# picopower.net
KiCad netlist of a schematic drawn in EAGLE
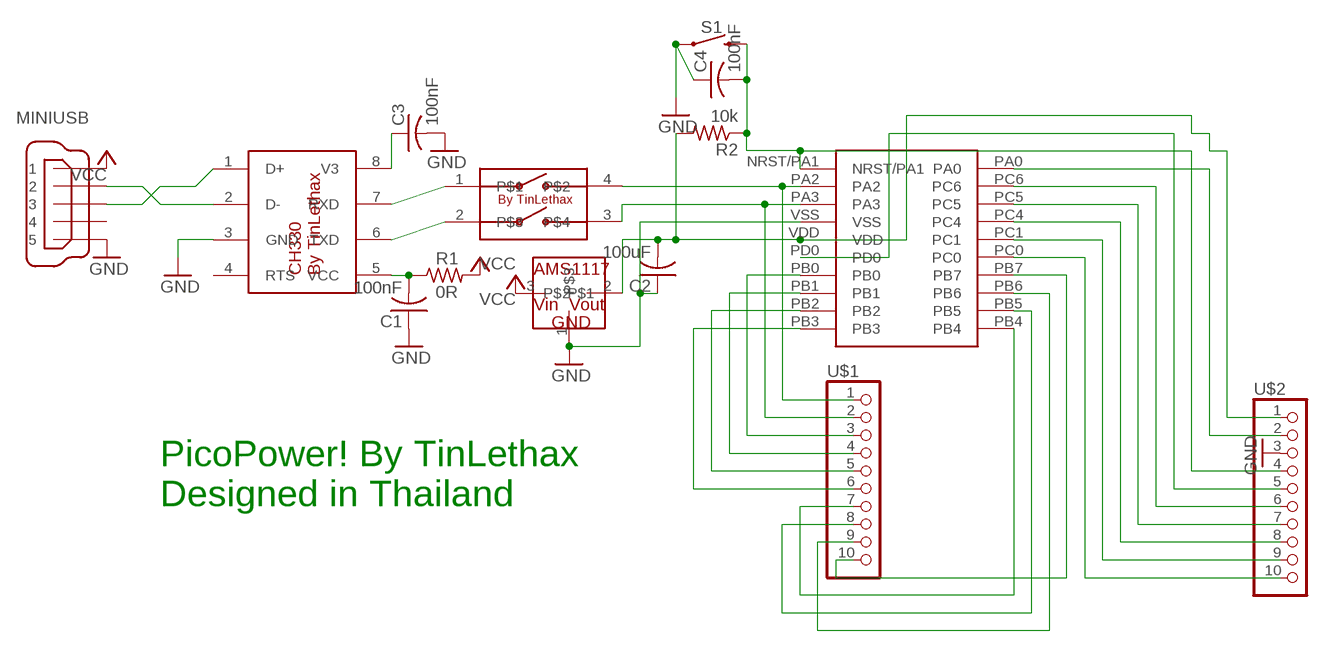
[diagram p0: schematic, sheet 1]

(export (version "E")
  (design (tool "Eeschema 10.0.6"))
  (components
    (comp (ref "2DIP")
      (value "2DIPSWITCH")
      (footprint "eagle-import:SOIC127P835X230-4N")
      (libsource (lib "eagle-import") (part "2DIPSWITCH"))
    )
    (comp (ref "C1")
      (value "100nF")
      (footprint "eagle-import:C0603K")
      (libsource (lib "eagle-import") (part "C-USC0603K"))
    )
    (comp (ref "C2")
      (value "100uF")
      (footprint "eagle-import:C0603K")
      (libsource (lib "eagle-import") (part "C-USC0603K"))
    )
    (comp (ref "C3")
      (value "100nF")
      (footprint "eagle-import:C0603K")
      (libsource (lib "eagle-import") (part "C-USC0603K"))
    )
    (comp (ref "C4")
      (value "100nF")
      (footprint "eagle-import:C0603K")
      (libsource (lib "eagle-import") (part "C-USC0603K"))
    )
    (comp (ref "CH330")
      (value "CH330")
      (footprint "eagle-import:SOIC127P600X150-8N")
      (libsource (lib "eagle-import") (part "CH330"))
    )
    (comp (ref "MINIUSB")
      (value "MINI-USB-UX60A-MB-5ST")
      (footprint "eagle-import:UX60A-MB-5ST")
      (libsource (lib "eagle-import") (part "MINI-USB-UX60A-MB-5ST"))
    )
    (comp (ref "R1")
      (value "0R")
      (footprint "eagle-import:R0603")
      (libsource (lib "eagle-import") (part "R-US_R0603"))
    )
    (comp (ref "R2")
      (value "10k")
      (footprint "eagle-import:R0603")
      (libsource (lib "eagle-import") (part "R-US_R0603"))
    )
    (comp (ref "S1")
      (value "MOMENTARY-SWITCH-SPST-SMD-6.0X3.5MM")
      (footprint "eagle-import:TACTILE_SWITCH_SMD_6.0X3.5MM")
      (libsource (lib "eagle-import") (part "MOMENTARY-SWITCH-SPST-SMD-6.0X3.5MM"))
    )
    (comp (ref "STM8L")
      (value "STM8L151F3")
      (footprint "eagle-import:UFQFPN-20")
      (libsource (lib "eagle-import") (part "STM8L151F3"))
    )
    (comp (ref "U$1")
      (value "PINHD-1X10")
      (footprint "eagle-import:1X10-BIG")
      (libsource (lib "eagle-import") (part "PINHD-1X10"))
    )
    (comp (ref "U$2")
      (value "PINHD-1X10")
      (footprint "eagle-import:1X10-BIG")
      (libsource (lib "eagle-import") (part "PINHD-1X10"))
    )
    (comp (ref "U$3")
      (value "AMS1117")
      (footprint "eagle-import:SOT223")
      (libsource (lib "eagle-import") (part "AMS1117"))
    )
  )
  (nets
    (net (code "1") (name "GND") (class "Default")
      (node (ref "C1") (pin "1") (pinfunction "1_1") (pintype "passive"))
      (node (ref "C2") (pin "1") (pinfunction "1_1") (pintype "passive"))
      (node (ref "C3") (pin "2") (pinfunction "2_2") (pintype "passive"))
      (node (ref "C4") (pin "1") (pinfunction "1_1") (pintype "passive"))
      (node (ref "CH330") (pin "3") (pinfunction "GND_3") (pintype "bidirectional"))
      (node (ref "MINIUSB") (pin "5") (pinfunction "5_5") (pintype "input"))
      (node (ref "S1") (pin "1") (pinfunction "1_1") (pintype "passive"))
      (node (ref "STM8L") (pin "VSS") (pinfunction "VSS_VSS") (pintype "bidirectional"))
      (node (ref "U$2") (pin "3") (pinfunction "3_3") (pintype "passive"))
      (node (ref "U$3") (pin "1") (pinfunction "P$3_1") (pintype "bidirectional"))
    )
    (net (code "2") (name "Net-(2DIP-P$1)") (class "Default")
      (node (ref "2DIP") (pin "1") (pinfunction "P$1_1") (pintype "bidirectional"))
      (node (ref "CH330") (pin "7") (pinfunction "RXD_7") (pintype "bidirectional"))
    )
    (net (code "3") (name "Net-(2DIP-P$2)") (class "Default")
      (node (ref "2DIP") (pin "4") (pinfunction "P$2_4") (pintype "bidirectional"))
      (node (ref "STM8L") (pin "PA2") (pinfunction "PA2_PA2") (pintype "bidirectional"))
      (node (ref "U$1") (pin "1") (pinfunction "1_1") (pintype "passive"))
    )
    (net (code "4") (name "Net-(2DIP-P$3)") (class "Default")
      (node (ref "2DIP") (pin "2") (pinfunction "P$3_2") (pintype "bidirectional"))
      (node (ref "CH330") (pin "6") (pinfunction "TXD_6") (pintype "bidirectional"))
    )
    (net (code "5") (name "Net-(2DIP-P$4)") (class "Default")
      (node (ref "2DIP") (pin "3") (pinfunction "P$4_3") (pintype "bidirectional"))
      (node (ref "STM8L") (pin "PA3") (pinfunction "PA3_PA3") (pintype "bidirectional"))
      (node (ref "U$1") (pin "2") (pinfunction "2_2") (pintype "passive"))
    )
    (net (code "6") (name "Net-(C4-Pad2)") (class "Default")
      (node (ref "C4") (pin "2") (pinfunction "2_2") (pintype "passive"))
      (node (ref "R2") (pin "1") (pinfunction "1_1") (pintype "passive"))
      (node (ref "S1") (pin "2") (pinfunction "2_2") (pintype "passive"))
      (node (ref "STM8L") (pin "NRST/PA1") (pinfunction "NRST/PA1_NRST/PA1") (pintype "bidirectional"))
      (node (ref "U$2") (pin "4") (pinfunction "4_4") (pintype "passive"))
    )
    (net (code "7") (name "Net-(CH330-D+)") (class "Default")
      (node (ref "CH330") (pin "1") (pinfunction "D+_1") (pintype "bidirectional"))
      (node (ref "MINIUSB") (pin "3") (pinfunction "3_3") (pintype "input"))
    )
    (net (code "8") (name "Net-(CH330-D-)") (class "Default")
      (node (ref "CH330") (pin "2") (pinfunction "D-_2") (pintype "bidirectional"))
      (node (ref "MINIUSB") (pin "2") (pinfunction "2_2") (pintype "input"))
    )
    (net (code "9") (name "Net-(CH330-V3)") (class "Default")
      (node (ref "C3") (pin "1") (pinfunction "1_1") (pintype "passive"))
      (node (ref "CH330") (pin "8") (pinfunction "V3_8") (pintype "bidirectional"))
    )
    (net (code "10") (name "Net-(CH330-VCC)") (class "Default")
      (node (ref "C1") (pin "2") (pinfunction "2_2") (pintype "passive"))
      (node (ref "CH330") (pin "5") (pinfunction "VCC_5") (pintype "bidirectional"))
      (node (ref "R1") (pin "1") (pinfunction "1_1") (pintype "passive"))
    )
    (net (code "11") (name "Net-(STM8L-PadPA0)") (class "Default")
      (node (ref "STM8L") (pin "PA0") (pinfunction "PA0_PA0") (pintype "bidirectional"))
      (node (ref "U$2") (pin "2") (pinfunction "2_2") (pintype "passive"))
    )
    (net (code "12") (name "Net-(STM8L-PadPB0)") (class "Default")
      (node (ref "STM8L") (pin "PB0") (pinfunction "PB0_PB0") (pintype "bidirectional"))
      (node (ref "U$1") (pin "3") (pinfunction "3_3") (pintype "passive"))
    )
    (net (code "13") (name "Net-(STM8L-PadPB1)") (class "Default")
      (node (ref "STM8L") (pin "PB1") (pinfunction "PB1_PB1") (pintype "bidirectional"))
      (node (ref "U$1") (pin "4") (pinfunction "4_4") (pintype "passive"))
    )
    (net (code "14") (name "Net-(STM8L-PadPB2)") (class "Default")
      (node (ref "STM8L") (pin "PB2") (pinfunction "PB2_PB2") (pintype "bidirectional"))
      (node (ref "U$1") (pin "5") (pinfunction "5_5") (pintype "passive"))
    )
    (net (code "15") (name "Net-(STM8L-PadPB3)") (class "Default")
      (node (ref "STM8L") (pin "PB3") (pinfunction "PB3_PB3") (pintype "bidirectional"))
      (node (ref "U$1") (pin "6") (pinfunction "6_6") (pintype "passive"))
    )
    (net (code "16") (name "Net-(STM8L-PadPB4)") (class "Default")
      (node (ref "STM8L") (pin "PB4") (pinfunction "PB4_PB4") (pintype "bidirectional"))
      (node (ref "U$1") (pin "7") (pinfunction "7_7") (pintype "passive"))
    )
    (net (code "17") (name "Net-(STM8L-PadPB5)") (class "Default")
      (node (ref "STM8L") (pin "PB5") (pinfunction "PB5_PB5") (pintype "bidirectional"))
      (node (ref "U$1") (pin "8") (pinfunction "8_8") (pintype "passive"))
    )
    (net (code "18") (name "Net-(STM8L-PadPB6)") (class "Default")
      (node (ref "STM8L") (pin "PB6") (pinfunction "PB6_PB6") (pintype "bidirectional"))
      (node (ref "U$1") (pin "9") (pinfunction "9_9") (pintype "passive"))
    )
    (net (code "19") (name "Net-(STM8L-PadPB7)") (class "Default")
      (node (ref "STM8L") (pin "PB7") (pinfunction "PB7_PB7") (pintype "bidirectional"))
      (node (ref "U$1") (pin "10") (pinfunction "10_10") (pintype "passive"))
    )
    (net (code "20") (name "Net-(STM8L-PadPC0)") (class "Default")
      (node (ref "STM8L") (pin "PC0") (pinfunction "PC0_PC0") (pintype "bidirectional"))
      (node (ref "U$2") (pin "10") (pinfunction "10_10") (pintype "passive"))
    )
    (net (code "21") (name "Net-(STM8L-PadPC1)") (class "Default")
      (node (ref "STM8L") (pin "PC1") (pinfunction "PC1_PC1") (pintype "bidirectional"))
      (node (ref "U$2") (pin "9") (pinfunction "9_9") (pintype "passive"))
    )
    (net (code "22") (name "Net-(STM8L-PadPC4)") (class "Default")
      (node (ref "STM8L") (pin "PC4") (pinfunction "PC4_PC4") (pintype "bidirectional"))
      (node (ref "U$2") (pin "8") (pinfunction "8_8") (pintype "passive"))
    )
    (net (code "23") (name "Net-(STM8L-PadPC5)") (class "Default")
      (node (ref "STM8L") (pin "PC5") (pinfunction "PC5_PC5") (pintype "bidirectional"))
      (node (ref "U$2") (pin "7") (pinfunction "7_7") (pintype "passive"))
    )
    (net (code "24") (name "Net-(STM8L-PadPC6)") (class "Default")
      (node (ref "STM8L") (pin "PC6") (pinfunction "PC6_PC6") (pintype "bidirectional"))
      (node (ref "U$2") (pin "6") (pinfunction "6_6") (pintype "passive"))
    )
    (net (code "25") (name "Net-(STM8L-PadPD0)") (class "Default")
      (node (ref "STM8L") (pin "PD0") (pinfunction "PD0_PD0") (pintype "bidirectional"))
      (node (ref "U$2") (pin "5") (pinfunction "5_5") (pintype "passive"))
    )
    (net (code "26") (name "Net-(U$3-P$2)") (class "Default")
      (node (ref "C2") (pin "2") (pinfunction "2_2") (pintype "passive"))
      (node (ref "R2") (pin "2") (pinfunction "2_2") (pintype "passive"))
      (node (ref "STM8L") (pin "VDD") (pinfunction "VDD_VDD") (pintype "bidirectional"))
      (node (ref "U$2") (pin "1") (pinfunction "1_1") (pintype "passive"))
      (node (ref "U$3") (pin "2") (pinfunction "P$2_2") (pintype "bidirectional"))
    )
    (net (code "27") (name "VCC") (class "Default")
      (node (ref "MINIUSB") (pin "1") (pinfunction "1_1") (pintype "input"))
      (node (ref "R1") (pin "2") (pinfunction "2_2") (pintype "passive"))
      (node (ref "U$3") (pin "3") (pinfunction "P$1_3") (pintype "bidirectional"))
    )
    (net (code "28") (name "unconnected-(CH330-RTS-Pad4)") (class "Default")
      (node (ref "CH330") (pin "4") (pinfunction "RTS_4") (pintype "bidirectional"))
    )
    (net (code "29") (name "unconnected-(MINIUSB-Pad4)") (class "Default")
      (node (ref "MINIUSB") (pin "4") (pinfunction "4_4") (pintype "input"))
    )
  )
)
